# Grillo_v_0_1.net
KiCad netlist of a schematic drawn in EAGLE
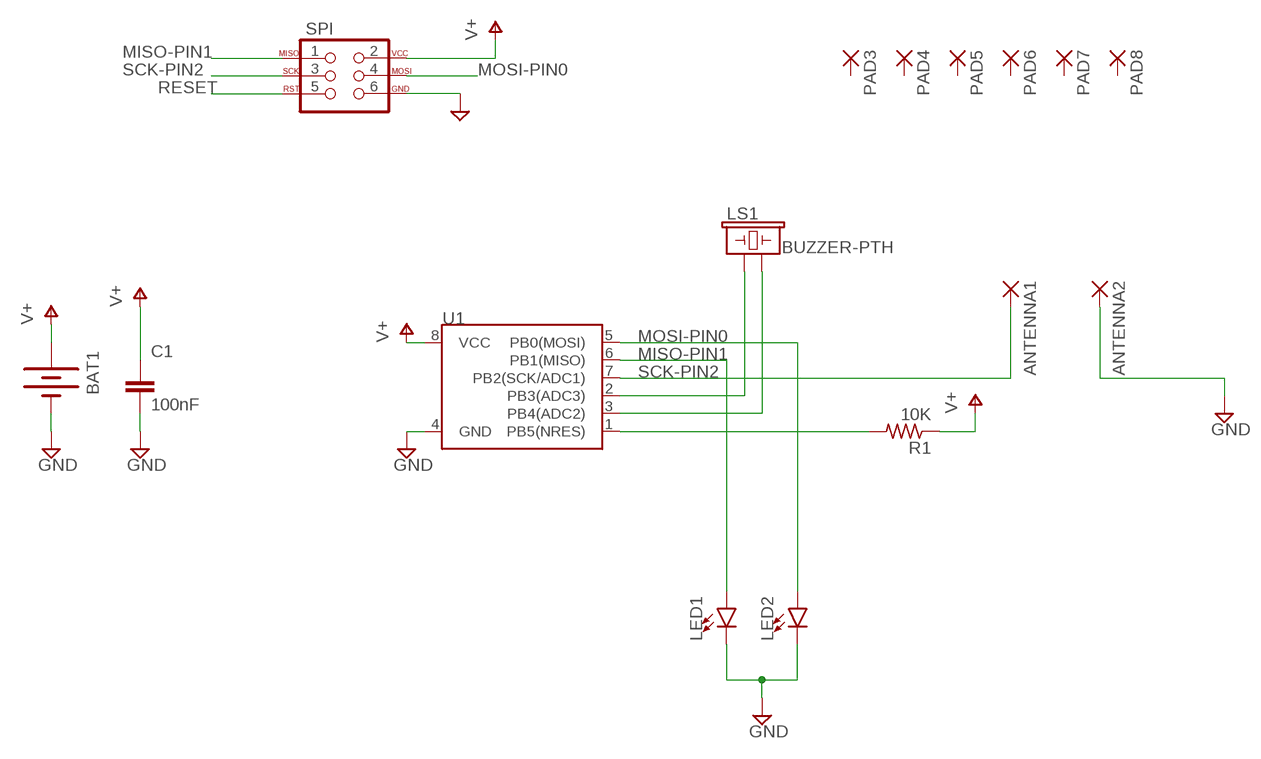
[diagram p0: schematic, sheet 1]

(export (version "E")
  (design (tool "Eeschema 10.0.6"))
  (components
    (comp (ref "ANTENNA1")
      (value "1,6/0,9")
      (footprint "eagle-import:1,6_0,9")
      (libsource (lib "eagle-import") (part "1,6/0,9"))
    )
    (comp (ref "ANTENNA2")
      (value "1,6/0,9")
      (footprint "eagle-import:1,6_0,9")
      (libsource (lib "eagle-import") (part "1,6/0,9"))
    )
    (comp (ref "BAT1")
      (value "BATTERY20PTH")
      (footprint "eagle-import:BATTCOM_20MM_PTH")
      (libsource (lib "eagle-import") (part "BATTERY20PTH"))
    )
    (comp (ref "C1")
      (value "100nF")
      (footprint "eagle-import:C050-024X044")
      (libsource (lib "eagle-import") (part "C-EU050-024X044"))
    )
    (comp (ref "LED1")
      (value "LED3MM")
      (footprint "eagle-import:LED_3MM")
      (libsource (lib "eagle-import") (part "LED3MM"))
    )
    (comp (ref "LED2")
      (value "LED3MM")
      (footprint "eagle-import:LED_3MM")
      (libsource (lib "eagle-import") (part "LED3MM"))
    )
    (comp (ref "LS1")
      (value "BUZZER-PTH")
      (footprint "eagle-import:BUZZER-12MM")
      (libsource (lib "eagle-import") (part "BUZZER-PTH"))
    )
    (comp (ref "PAD3")
      (value "1,6/0,9")
      (footprint "eagle-import:1,6_0,9")
      (libsource (lib "eagle-import") (part "1,6/0,9"))
    )
    (comp (ref "PAD4")
      (value "1,6/0,9")
      (footprint "eagle-import:1,6_0,9")
      (libsource (lib "eagle-import") (part "1,6/0,9"))
    )
    (comp (ref "PAD5")
      (value "1,6/0,9")
      (footprint "eagle-import:1,6_0,9")
      (libsource (lib "eagle-import") (part "1,6/0,9"))
    )
    (comp (ref "PAD6")
      (value "1,6/0,9")
      (footprint "eagle-import:1,6_0,9")
      (libsource (lib "eagle-import") (part "1,6/0,9"))
    )
    (comp (ref "PAD7")
      (value "1,6/0,9")
      (footprint "eagle-import:1,6_0,9")
      (libsource (lib "eagle-import") (part "1,6/0,9"))
    )
    (comp (ref "PAD8")
      (value "1,6/0,9")
      (footprint "eagle-import:1,6_0,9")
      (libsource (lib "eagle-import") (part "1,6/0,9"))
    )
    (comp (ref "R1")
      (value "10K")
      (footprint "eagle-import:0204_7")
      (libsource (lib "eagle-import") (part "R-US_0204/7"))
    )
    (comp (ref "SPI")
      (value "AVR_SPI_PROG_3X2PTH")
      (footprint "eagle-import:2X3")
      (libsource (lib "eagle-import") (part "AVR_SPI_PROG_3X2PTH"))
    )
    (comp (ref "U1")
      (value "ATTINY45TINY85-20-DIP")
      (footprint "eagle-import:DIP08")
      (libsource (lib "eagle-import") (part "ATTINY45TINY85-20-DIP"))
    )
  )
  (nets
    (net (code "1") (name "/MISO-PIN1") (class "Default")
      (node (ref "LED1") (pin "A") (pinfunction "A_A") (pintype "passive"))
      (node (ref "SPI") (pin "1") (pinfunction "1_1") (pintype "passive"))
      (node (ref "U1") (pin "6") (pinfunction "PB1(MISO)_6") (pintype "bidirectional"))
    )
    (net (code "2") (name "/MOSI-PIN0") (class "Default")
      (node (ref "LED2") (pin "A") (pinfunction "A_A") (pintype "passive"))
      (node (ref "SPI") (pin "4") (pinfunction "4_4") (pintype "passive"))
      (node (ref "U1") (pin "5") (pinfunction "PB0(MOSI)_5") (pintype "bidirectional"))
    )
    (net (code "3") (name "/RESET") (class "Default")
      (node (ref "R1") (pin "2") (pinfunction "2_2") (pintype "passive"))
      (node (ref "SPI") (pin "5") (pinfunction "5_5") (pintype "passive"))
      (node (ref "U1") (pin "1") (pinfunction "PB5(NRES)_1") (pintype "bidirectional"))
    )
    (net (code "4") (name "/SCK-PIN2") (class "Default")
      (node (ref "ANTENNA1") (pin "1") (pinfunction "P_1") (pintype "passive"))
      (node (ref "SPI") (pin "3") (pinfunction "3_3") (pintype "passive"))
      (node (ref "U1") (pin "7") (pinfunction "PB2(SCK/ADC1)_7") (pintype "bidirectional"))
    )
    (net (code "5") (name "GND") (class "Default")
      (node (ref "ANTENNA2") (pin "1") (pinfunction "P_1") (pintype "passive"))
      (node (ref "BAT1") (pin "2") (pinfunction "-_2") (pintype "power_in"))
      (node (ref "C1") (pin "2") (pinfunction "2_2") (pintype "passive"))
      (node (ref "LED1") (pin "K") (pinfunction "C_K") (pintype "passive"))
      (node (ref "LED2") (pin "K") (pinfunction "C_K") (pintype "passive"))
      (node (ref "SPI") (pin "6") (pinfunction "6_6") (pintype "passive"))
      (node (ref "U1") (pin "4") (pinfunction "GND_4") (pintype "bidirectional"))
    )
    (net (code "6") (name "Net-(LS1-1)") (class "Default")
      (node (ref "LS1") (pin "+") (pinfunction "1_+") (pintype "passive"))
      (node (ref "U1") (pin "2") (pinfunction "PB3(ADC3)_2") (pintype "bidirectional"))
    )
    (net (code "7") (name "Net-(LS1-2)") (class "Default")
      (node (ref "LS1") (pin "-") (pinfunction "2_-") (pintype "passive"))
      (node (ref "U1") (pin "3") (pinfunction "PB4(ADC2)_3") (pintype "bidirectional"))
    )
    (net (code "8") (name "V+") (class "Default")
      (node (ref "BAT1") (pin "1") (pinfunction "+_1") (pintype "power_in"))
      (node (ref "C1") (pin "1") (pinfunction "1_1") (pintype "passive"))
      (node (ref "R1") (pin "1") (pinfunction "1_1") (pintype "passive"))
      (node (ref "SPI") (pin "2") (pinfunction "2_2") (pintype "passive"))
      (node (ref "U1") (pin "8") (pinfunction "VCC_8") (pintype "bidirectional"))
    )
    (net (code "9") (name "unconnected-(PAD3-P-Pad1)") (class "Default")
      (node (ref "PAD3") (pin "1") (pinfunction "P_1") (pintype "passive"))
    )
    (net (code "10") (name "unconnected-(PAD4-P-Pad1)") (class "Default")
      (node (ref "PAD4") (pin "1") (pinfunction "P_1") (pintype "passive"))
    )
    (net (code "11") (name "unconnected-(PAD5-P-Pad1)") (class "Default")
      (node (ref "PAD5") (pin "1") (pinfunction "P_1") (pintype "passive"))
    )
    (net (code "12") (name "unconnected-(PAD6-P-Pad1)") (class "Default")
      (node (ref "PAD6") (pin "1") (pinfunction "P_1") (pintype "passive"))
    )
    (net (code "13") (name "unconnected-(PAD7-P-Pad1)") (class "Default")
      (node (ref "PAD7") (pin "1") (pinfunction "P_1") (pintype "passive"))
    )
    (net (code "14") (name "unconnected-(PAD8-P-Pad1)") (class "Default")
      (node (ref "PAD8") (pin "1") (pinfunction "P_1") (pintype "passive"))
    )
  )
)
